# Adafruit_AT42QT1012_Breakout.net
KiCad netlist of a schematic drawn in EAGLE
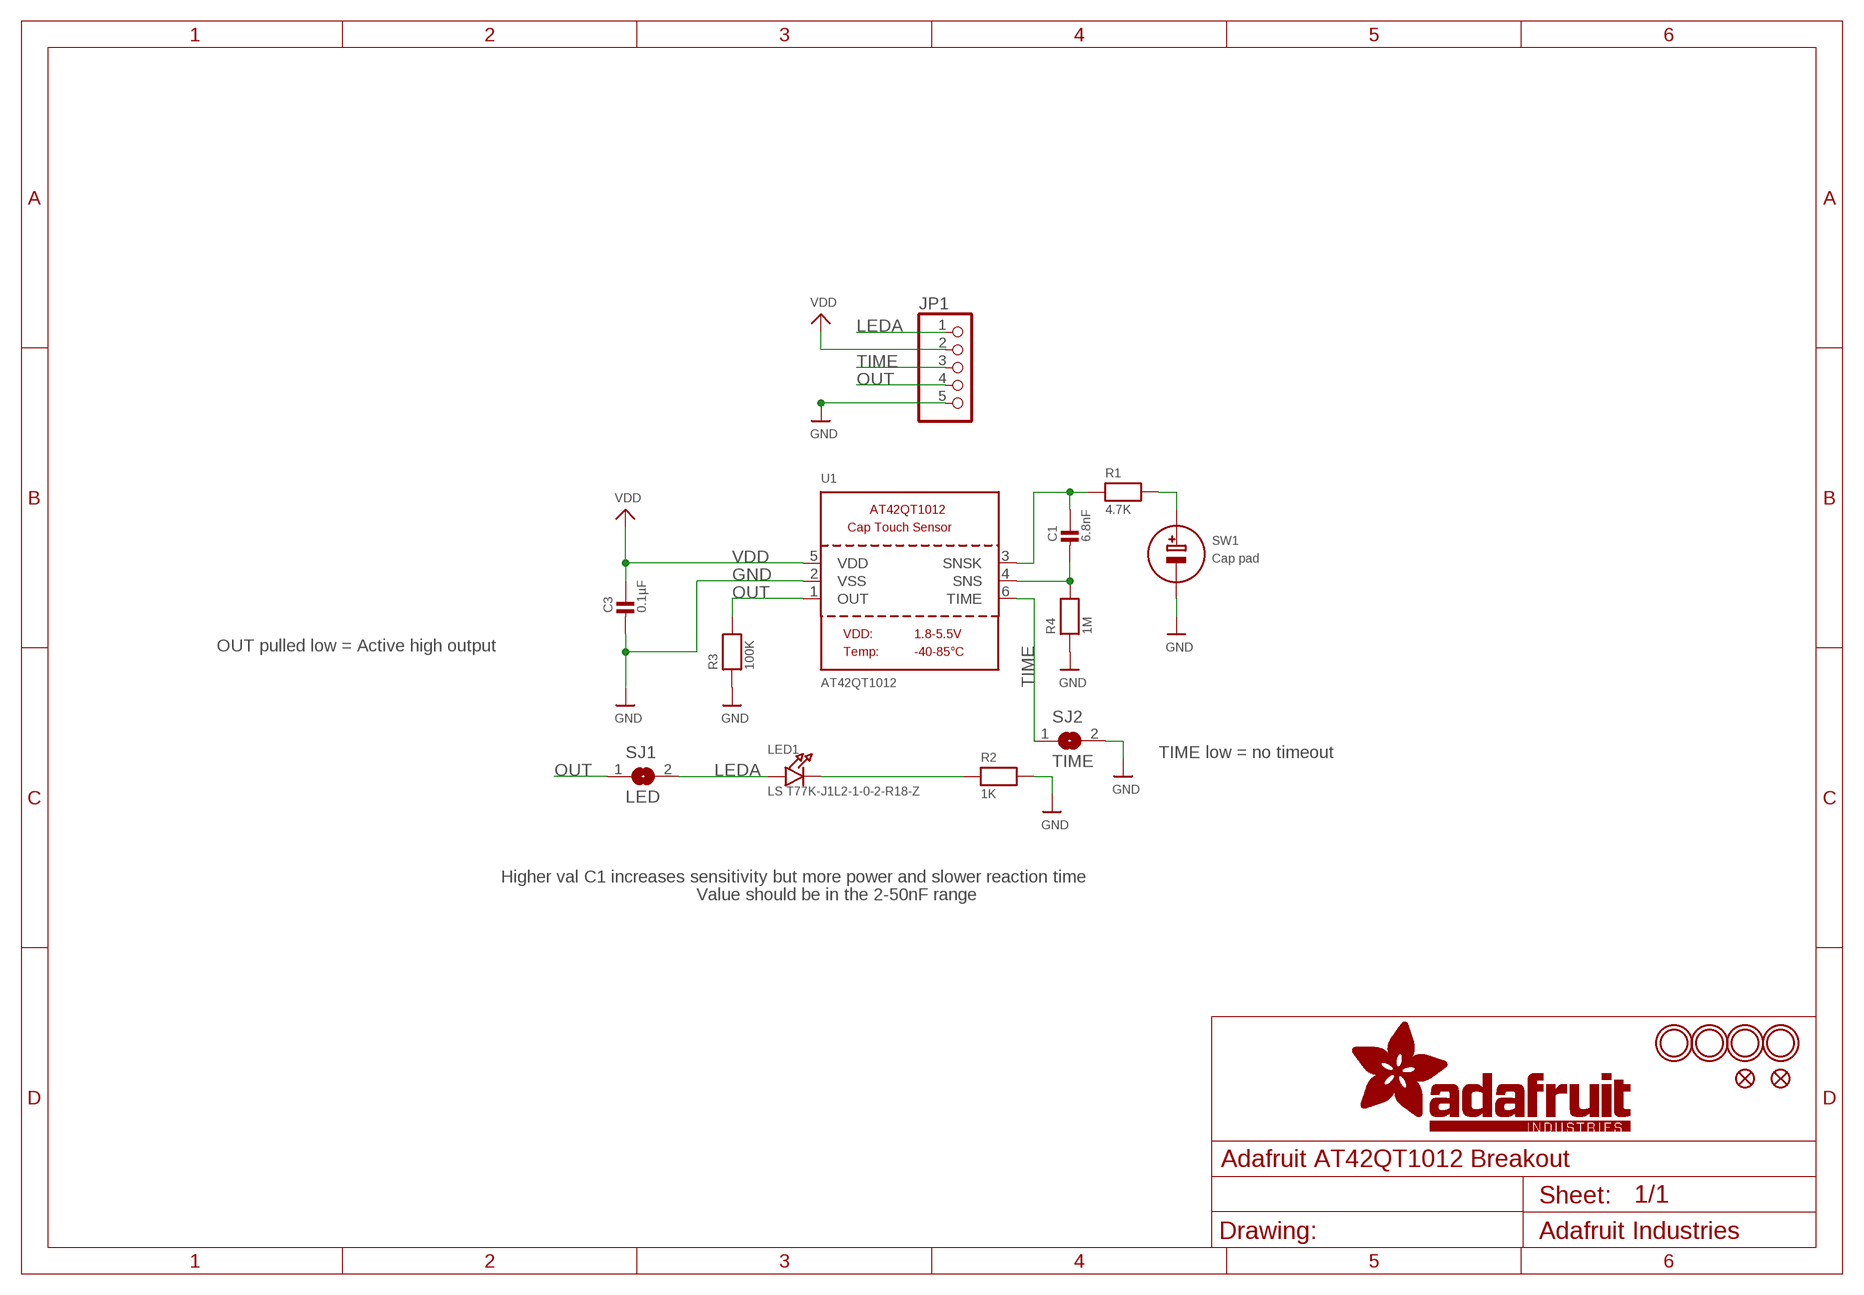
[diagram p0: schematic, sheet 1]

(export (version "E")
  (design (tool "Eeschema 10.0.6"))
  (components
    (comp (ref "C1")
      (value "6.8nF")
      (footprint "eagle-import:_0805")
      (libsource (lib "eagle-import") (part "CAP_CERAMIC_0805"))
    )
    (comp (ref "C3")
      (value "0.1µF")
      (footprint "eagle-import:_0805")
      (libsource (lib "eagle-import") (part "CAP_CERAMIC_0805"))
    )
    (comp (ref "FID1")
      (value "FIDUCIAL\"\"")
      (footprint "eagle-import:FIDUCIAL_1MM")
      (libsource (lib "eagle-import") (part "FIDUCIAL{dblquote}{dblquote}"))
    )
    (comp (ref "FID2")
      (value "FIDUCIAL\"\"")
      (footprint "eagle-import:FIDUCIAL_1MM")
      (libsource (lib "eagle-import") (part "FIDUCIAL{dblquote}{dblquote}"))
    )
    (comp (ref "JP1")
      (value "HEADER-1X570MIL")
      (footprint "eagle-import:1X05_ROUND_70")
      (libsource (lib "eagle-import") (part "HEADER-1X570MIL"))
    )
    (comp (ref "LED1")
      (value "LS T77K-J1L2-1-0-2-R18-Z")
      (footprint "eagle-import:PLCC2_REVMOUNT")
      (libsource (lib "eagle-import") (part "LEDPLCC2_REV"))
    )
    (comp (ref "R1")
      (value "4.7K")
      (footprint "eagle-import:_0805")
      (libsource (lib "eagle-import") (part "RESISTOR_0805"))
    )
    (comp (ref "R2")
      (value "1K")
      (footprint "eagle-import:_0805")
      (libsource (lib "eagle-import") (part "RESISTOR_0805"))
    )
    (comp (ref "R3")
      (value "100K")
      (footprint "eagle-import:_0805")
      (libsource (lib "eagle-import") (part "RESISTOR_0805"))
    )
    (comp (ref "R4")
      (value "1M")
      (footprint "eagle-import:_0805")
      (libsource (lib "eagle-import") (part "RESISTOR_0805"))
    )
    (comp (ref "SJ1")
      (value "LED")
      (footprint "eagle-import:SOLDERJUMPER_CLOSEDWIRE")
      (libsource (lib "eagle-import") (part "SOLDERJUMPERCLOSED"))
    )
    (comp (ref "SJ2")
      (value "TIME")
      (footprint "eagle-import:SOLDERJUMPER_CLOSEDWIRE")
      (libsource (lib "eagle-import") (part "SOLDERJUMPERCLOSED"))
    )
    (comp (ref "SW1")
      (value "Cap pad")
      (footprint "eagle-import:CAPTOUCH_SIMPLE_12.5MM")
      (libsource (lib "eagle-import") (part "SWITCH_CAPTOUCHATMELAT42QT"))
    )
    (comp (ref "U$6")
      (value "MOUNTINGHOLE2.5")
      (footprint "eagle-import:MOUNTINGHOLE_2.5_PLATED")
      (libsource (lib "eagle-import") (part "MOUNTINGHOLE2.5"))
    )
    (comp (ref "U$9")
      (value "MOUNTINGHOLE2.5")
      (footprint "eagle-import:MOUNTINGHOLE_2.5_PLATED")
      (libsource (lib "eagle-import") (part "MOUNTINGHOLE2.5"))
    )
    (comp (ref "U$10")
      (value "MOUNTINGHOLE2.5")
      (footprint "eagle-import:MOUNTINGHOLE_2.5_PLATED")
      (libsource (lib "eagle-import") (part "MOUNTINGHOLE2.5"))
    )
    (comp (ref "U$11")
      (value "MOUNTINGHOLE2.5")
      (footprint "eagle-import:MOUNTINGHOLE_2.5_PLATED")
      (libsource (lib "eagle-import") (part "MOUNTINGHOLE2.5"))
    )
    (comp (ref "U1")
      (value "AT42QT1012")
      (footprint "eagle-import:SOT23-6")
      (libsource (lib "eagle-import") (part "AT42QT1012"))
    )
  )
  (nets
    (net (code "1") (name "/LEDA") (class "Default")
      (node (ref "JP1") (pin "1") (pinfunction "1_1") (pintype "passive"))
      (node (ref "LED1") (pin "A") (pinfunction "A_A") (pintype "passive"))
      (node (ref "SJ1") (pin "2") (pinfunction "2_2") (pintype "passive"))
    )
    (net (code "2") (name "/OUT") (class "Default")
      (node (ref "JP1") (pin "4") (pinfunction "4_4") (pintype "passive"))
      (node (ref "R3") (pin "2") (pinfunction "2_2") (pintype "passive"))
      (node (ref "SJ1") (pin "1") (pinfunction "1_1") (pintype "passive"))
      (node (ref "U1") (pin "1") (pinfunction "OUT_1") (pintype "output"))
    )
    (net (code "3") (name "/TIME") (class "Default")
      (node (ref "JP1") (pin "3") (pinfunction "3_3") (pintype "passive"))
      (node (ref "SJ2") (pin "1") (pinfunction "1_1") (pintype "passive"))
      (node (ref "U1") (pin "6") (pinfunction "TIME_6") (pintype "input"))
    )
    (net (code "4") (name "GND") (class "Default")
      (node (ref "C3") (pin "2") (pinfunction "P$2_2") (pintype "passive"))
      (node (ref "JP1") (pin "5") (pinfunction "5_5") (pintype "passive"))
      (node (ref "R2") (pin "2") (pinfunction "2_2") (pintype "passive"))
      (node (ref "R3") (pin "1") (pinfunction "1_1") (pintype "passive"))
      (node (ref "R4") (pin "1") (pinfunction "1_1") (pintype "passive"))
      (node (ref "SJ2") (pin "2") (pinfunction "2_2") (pintype "passive"))
      (node (ref "SW1") (pin "G") (pinfunction "-_G") (pintype "passive"))
      (node (ref "U1") (pin "2") (pinfunction "VSS_2") (pintype "power_in"))
    )
    (net (code "5") (name "Net-(C1-P$1)") (class "Default")
      (node (ref "C1") (pin "1") (pinfunction "P$1_1") (pintype "passive"))
      (node (ref "R1") (pin "1") (pinfunction "1_1") (pintype "passive"))
      (node (ref "U1") (pin "3") (pinfunction "SNSK_3") (pintype "bidirectional"))
    )
    (net (code "6") (name "Net-(C1-P$2)") (class "Default")
      (node (ref "C1") (pin "2") (pinfunction "P$2_2") (pintype "passive"))
      (node (ref "R4") (pin "2") (pinfunction "2_2") (pintype "passive"))
      (node (ref "U1") (pin "4") (pinfunction "SNS_4") (pintype "bidirectional"))
    )
    (net (code "7") (name "Net-(LED1-C)") (class "Default")
      (node (ref "LED1") (pin "K") (pinfunction "C_K") (pintype "passive"))
      (node (ref "R2") (pin "1") (pinfunction "1_1") (pintype "passive"))
    )
    (net (code "8") (name "Net-(SW1-+)") (class "Default")
      (node (ref "R1") (pin "2") (pinfunction "2_2") (pintype "passive"))
      (node (ref "SW1") (pin "E") (pinfunction "+_E") (pintype "passive"))
    )
    (net (code "9") (name "VDD") (class "Default")
      (node (ref "C3") (pin "1") (pinfunction "P$1_1") (pintype "passive"))
      (node (ref "JP1") (pin "2") (pinfunction "2_2") (pintype "passive"))
      (node (ref "U1") (pin "5") (pinfunction "VDD_5") (pintype "power_in"))
    )
  )
)
